# cc2500.net
KiCad netlist of a schematic drawn in EAGLE
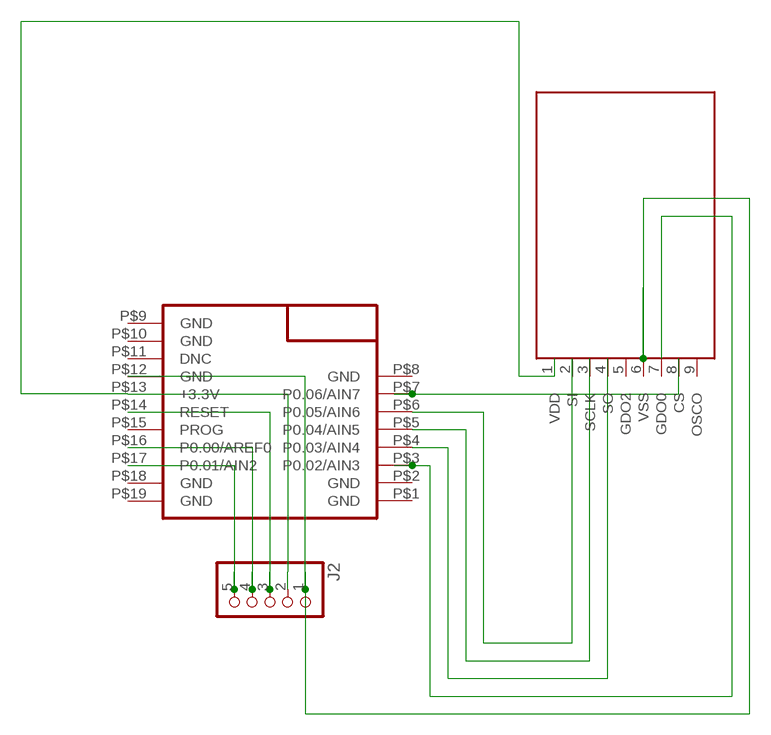
[diagram p0: schematic, sheet 1]

(export (version "E")
  (design (tool "Eeschema 10.0.6"))
  (components
    (comp (ref "J2")
      (value "PINHD-1X5")
      (footprint "eagle-import:1X05")
      (libsource (lib "eagle-import") (part "PINHD-1X5"))
    )
    (comp (ref "U$1")
      (value "RFD22301")
      (footprint "eagle-import:RFD21733")
      (libsource (lib "eagle-import") (part "RFD22301"))
    )
    (comp (ref "U$2")
      (value "CC2500-RADIO")
      (footprint "eagle-import:CC2500BOARD")
      (libsource (lib "eagle-import") (part "CC2500-RADIO"))
    )
  )
  (nets
    (net (code "1") (name "Net-(U$1-+3.3V)") (class "Default")
      (node (ref "J2") (pin "2") (pinfunction "2_2") (pintype "passive"))
      (node (ref "U$1") (pin "P$13") (pinfunction "+3.3V_P$13") (pintype "bidirectional"))
      (node (ref "U$2") (pin "1") (pinfunction "VDD_1") (pintype "bidirectional"))
    )
    (net (code "2") (name "Net-(U$1-P0.00{slash}AREF0)") (class "Default")
      (node (ref "J2") (pin "4") (pinfunction "4_4") (pintype "passive"))
      (node (ref "U$1") (pin "P$16") (pinfunction "P0.00/AREF0_P$16") (pintype "bidirectional"))
    )
    (net (code "3") (name "Net-(U$1-P0.01{slash}AIN2)") (class "Default")
      (node (ref "J2") (pin "5") (pinfunction "5_5") (pintype "passive"))
      (node (ref "U$1") (pin "P$17") (pinfunction "P0.01/AIN2_P$17") (pintype "bidirectional"))
    )
    (net (code "4") (name "Net-(U$1-P0.02{slash}AIN3)") (class "Default")
      (node (ref "U$1") (pin "P$3") (pinfunction "P0.02/AIN3_P$3") (pintype "bidirectional"))
      (node (ref "U$2") (pin "7") (pinfunction "GDO0_7") (pintype "bidirectional"))
    )
    (net (code "5") (name "Net-(U$1-P0.03{slash}AIN4)") (class "Default")
      (node (ref "U$1") (pin "P$4") (pinfunction "P0.03/AIN4_P$4") (pintype "bidirectional"))
      (node (ref "U$2") (pin "4") (pinfunction "SO_4") (pintype "bidirectional"))
    )
    (net (code "6") (name "Net-(U$1-P0.04{slash}AIN5)") (class "Default")
      (node (ref "U$1") (pin "P$5") (pinfunction "P0.04/AIN5_P$5") (pintype "bidirectional"))
      (node (ref "U$2") (pin "3") (pinfunction "SCLK_3") (pintype "bidirectional"))
    )
    (net (code "7") (name "Net-(U$1-P0.05{slash}AIN6)") (class "Default")
      (node (ref "U$1") (pin "P$6") (pinfunction "P0.05/AIN6_P$6") (pintype "bidirectional"))
      (node (ref "U$2") (pin "2") (pinfunction "SI_2") (pintype "bidirectional"))
    )
    (net (code "8") (name "Net-(U$1-P0.06{slash}AIN7)") (class "Default")
      (node (ref "U$1") (pin "P$7") (pinfunction "P0.06/AIN7_P$7") (pintype "bidirectional"))
      (node (ref "U$2") (pin "8") (pinfunction "CS_8") (pintype "bidirectional"))
    )
    (net (code "9") (name "Net-(U$1-RESET)") (class "Default")
      (node (ref "J2") (pin "3") (pinfunction "3_3") (pintype "passive"))
      (node (ref "U$1") (pin "P$14") (pinfunction "RESET_P$14") (pintype "bidirectional"))
    )
    (net (code "10") (name "Net-(U$2-VSS)") (class "Default")
      (node (ref "J2") (pin "1") (pinfunction "1_1") (pintype "passive"))
      (node (ref "U$1") (pin "P$12") (pinfunction "GND_P$12") (pintype "bidirectional"))
      (node (ref "U$2") (pin "6") (pinfunction "VSS_6") (pintype "bidirectional"))
    )
    (net (code "11") (name "unconnected-(U$1-DNC-PadP$11)") (class "Default")
      (node (ref "U$1") (pin "P$11") (pinfunction "DNC_P$11") (pintype "bidirectional"))
    )
    (net (code "12") (name "unconnected-(U$1-GND-PadP$1)") (class "Default")
      (node (ref "U$1") (pin "P$1") (pinfunction "GND_P$1") (pintype "bidirectional"))
    )
    (net (code "13") (name "unconnected-(U$1-GND-PadP$2)") (class "Default")
      (node (ref "U$1") (pin "P$2") (pinfunction "GND_P$2") (pintype "bidirectional"))
    )
    (net (code "14") (name "unconnected-(U$1-GND-PadP$8)") (class "Default")
      (node (ref "U$1") (pin "P$8") (pinfunction "GND_P$8") (pintype "bidirectional"))
    )
    (net (code "15") (name "unconnected-(U$1-GND-PadP$9)") (class "Default")
      (node (ref "U$1") (pin "P$9") (pinfunction "GND_P$9") (pintype "bidirectional"))
    )
    (net (code "16") (name "unconnected-(U$1-GND-PadP$10)") (class "Default")
      (node (ref "U$1") (pin "P$10") (pinfunction "GND_P$10") (pintype "bidirectional"))
    )
    (net (code "17") (name "unconnected-(U$1-GND-PadP$18)") (class "Default")
      (node (ref "U$1") (pin "P$18") (pinfunction "GND_P$18") (pintype "bidirectional"))
    )
    (net (code "18") (name "unconnected-(U$1-GND-PadP$19)") (class "Default")
      (node (ref "U$1") (pin "P$19") (pinfunction "GND_P$19") (pintype "bidirectional"))
    )
    (net (code "19") (name "unconnected-(U$1-PROG-PadP$15)") (class "Default")
      (node (ref "U$1") (pin "P$15") (pinfunction "PROG_P$15") (pintype "bidirectional"))
    )
    (net (code "20") (name "unconnected-(U$2-GDO2-Pad5)") (class "Default")
      (node (ref "U$2") (pin "5") (pinfunction "GDO2_5") (pintype "bidirectional"))
    )
    (net (code "21") (name "unconnected-(U$2-OSCO-Pad9)") (class "Default")
      (node (ref "U$2") (pin "9") (pinfunction "OSCO_9") (pintype "bidirectional"))
    )
  )
)
